# alexakit.net
KiCad netlist of a schematic drawn in EAGLE
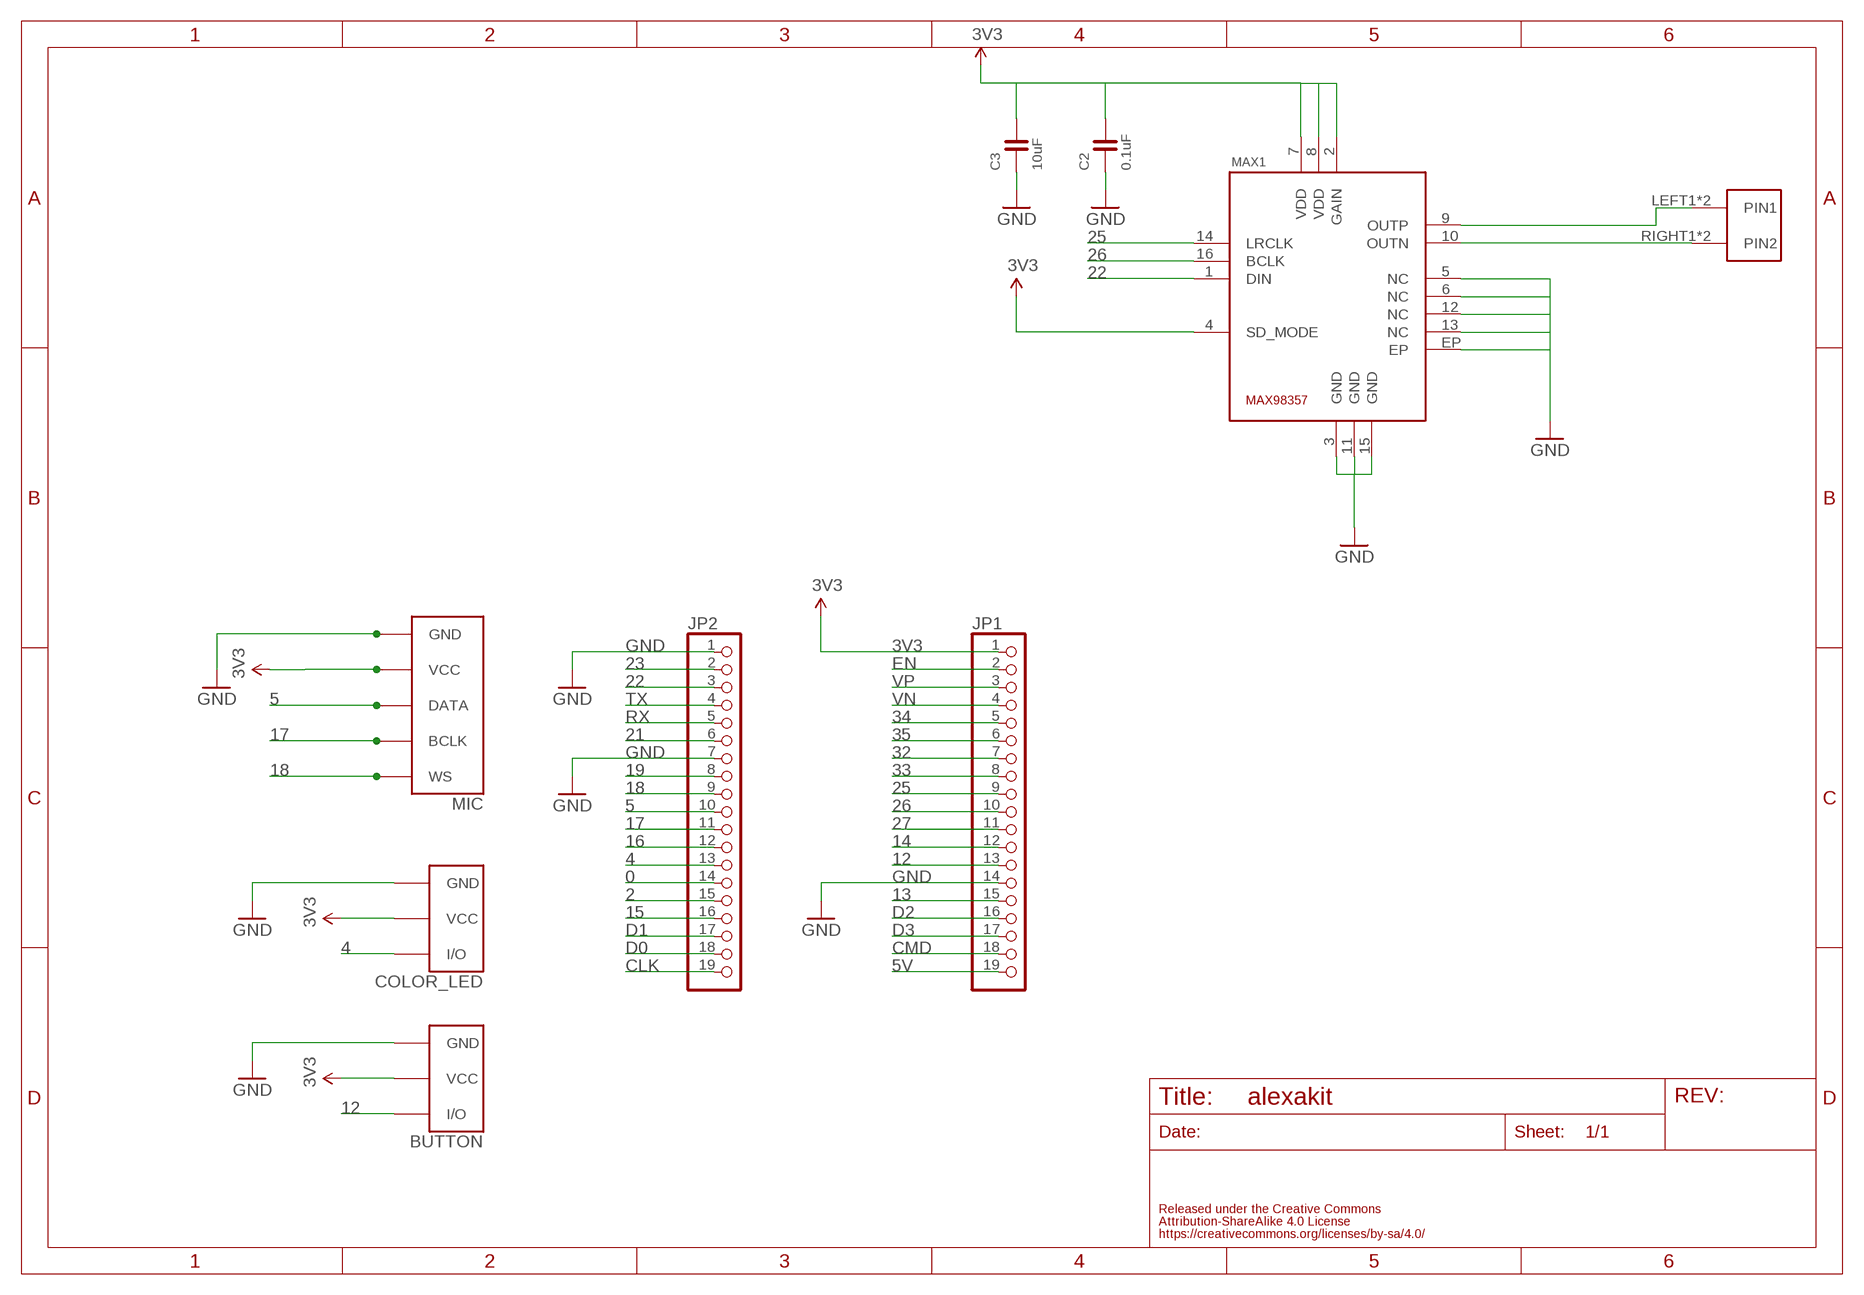
[diagram p0: schematic, sheet 1]

(export (version "E")
  (design (tool "Eeschema 10.0.6"))
  (components
    (comp (ref "BUTTON")
      (value "BUTTON")
      (footprint "eagle-import:FABO_BRICK_3PIN_B03B-PASK-1_NAME_BOTTOM")
      (libsource (lib "eagle-import") (part "FABO_BRICK_3PIN-03B-PASK-1_NAME_BOTTOM"))
    )
    (comp (ref "C2")
      (value "0.1uF")
      (footprint "eagle-import:0603")
      (libsource (lib "eagle-import") (part "CAPACITOR-0603"))
    )
    (comp (ref "C3")
      (value "10uF")
      (footprint "eagle-import:0603")
      (libsource (lib "eagle-import") (part "CAPACITOR-0603"))
    )
    (comp (ref "COLOR_LED")
      (value "FABO_BRICK_3PIN-03B-PASK-1_NAME_BOTTOM")
      (footprint "eagle-import:FABO_BRICK_3PIN_B03B-PASK-1_NAME_BOTTOM")
      (libsource (lib "eagle-import") (part "FABO_BRICK_3PIN-03B-PASK-1_NAME_BOTTOM"))
    )
    (comp (ref "JP1")
      (value "PINHD-1X19")
      (footprint "eagle-import:1X19")
      (libsource (lib "eagle-import") (part "PINHD-1X19"))
    )
    (comp (ref "JP2")
      (value "PINHD-1X19")
      (footprint "eagle-import:1X19")
      (libsource (lib "eagle-import") (part "PINHD-1X19"))
    )
    (comp (ref "MAX1")
      (value "MA-MAX98357")
      (footprint "eagle-import:MAXIM-MAX98357")
      (libsource (lib "eagle-import") (part "MA-MAX98357"))
    )
    (comp (ref "MIC")
      (value "FABO_BRICK_I2STOP")
      (footprint "eagle-import:FABO_BRICK_I2S_B05B-PARK-1")
      (libsource (lib "eagle-import") (part "FABO_BRICK_I2STOP"))
    )
    (comp (ref "U$4")
      (value "ML-1400-S1")
      (footprint "eagle-import:ML-1400-S1")
      (libsource (lib "eagle-import") (part "ML-1400-S1"))
    )
  )
  (nets
    (net (code "1") (name "/0") (class "Default")
      (node (ref "JP2") (pin "14") (pinfunction "14_14") (pintype "passive"))
    )
    (net (code "2") (name "/2") (class "Default")
      (node (ref "JP2") (pin "15") (pinfunction "15_15") (pintype "passive"))
    )
    (net (code "3") (name "/4") (class "Default")
      (node (ref "COLOR_LED") (pin "I/O") (pinfunction "I/O_I/O") (pintype "bidirectional"))
      (node (ref "JP2") (pin "13") (pinfunction "13_13") (pintype "passive"))
    )
    (net (code "4") (name "/5") (class "Default")
      (node (ref "JP2") (pin "10") (pinfunction "10_10") (pintype "passive"))
      (node (ref "MIC") (pin "DATA") (pinfunction "DATA_DATA") (pintype "bidirectional"))
    )
    (net (code "5") (name "/5V") (class "Default")
      (node (ref "JP1") (pin "19") (pinfunction "19_19") (pintype "passive"))
    )
    (net (code "6") (name "/12") (class "Default")
      (node (ref "BUTTON") (pin "I/O") (pinfunction "I/O_I/O") (pintype "bidirectional"))
      (node (ref "JP1") (pin "13") (pinfunction "13_13") (pintype "passive"))
    )
    (net (code "7") (name "/13") (class "Default")
      (node (ref "JP1") (pin "15") (pinfunction "15_15") (pintype "passive"))
    )
    (net (code "8") (name "/14") (class "Default")
      (node (ref "JP1") (pin "12") (pinfunction "12_12") (pintype "passive"))
    )
    (net (code "9") (name "/15") (class "Default")
      (node (ref "JP2") (pin "16") (pinfunction "16_16") (pintype "passive"))
    )
    (net (code "10") (name "/16") (class "Default")
      (node (ref "JP2") (pin "12") (pinfunction "12_12") (pintype "passive"))
    )
    (net (code "11") (name "/17") (class "Default")
      (node (ref "JP2") (pin "11") (pinfunction "11_11") (pintype "passive"))
      (node (ref "MIC") (pin "BCLK") (pinfunction "BCLK_BCLK") (pintype "bidirectional"))
    )
    (net (code "12") (name "/18") (class "Default")
      (node (ref "JP2") (pin "9") (pinfunction "9_9") (pintype "passive"))
      (node (ref "MIC") (pin "WS") (pinfunction "WS_WS") (pintype "bidirectional"))
    )
    (net (code "13") (name "/19") (class "Default")
      (node (ref "JP2") (pin "8") (pinfunction "8_8") (pintype "passive"))
    )
    (net (code "14") (name "/21") (class "Default")
      (node (ref "JP2") (pin "6") (pinfunction "6_6") (pintype "passive"))
    )
    (net (code "15") (name "/22") (class "Default")
      (node (ref "JP2") (pin "3") (pinfunction "3_3") (pintype "passive"))
      (node (ref "MAX1") (pin "1") (pinfunction "DIN_1") (pintype "bidirectional"))
    )
    (net (code "16") (name "/23") (class "Default")
      (node (ref "JP2") (pin "2") (pinfunction "2_2") (pintype "passive"))
    )
    (net (code "17") (name "/25") (class "Default")
      (node (ref "JP1") (pin "9") (pinfunction "9_9") (pintype "passive"))
      (node (ref "MAX1") (pin "14") (pinfunction "LRCLK_14") (pintype "bidirectional"))
    )
    (net (code "18") (name "/26") (class "Default")
      (node (ref "JP1") (pin "10") (pinfunction "10_10") (pintype "passive"))
      (node (ref "MAX1") (pin "16") (pinfunction "BCLK_16") (pintype "bidirectional"))
    )
    (net (code "19") (name "/27") (class "Default")
      (node (ref "JP1") (pin "11") (pinfunction "11_11") (pintype "passive"))
    )
    (net (code "20") (name "/32") (class "Default")
      (node (ref "JP1") (pin "7") (pinfunction "7_7") (pintype "passive"))
    )
    (net (code "21") (name "/33") (class "Default")
      (node (ref "JP1") (pin "8") (pinfunction "8_8") (pintype "passive"))
    )
    (net (code "22") (name "/34") (class "Default")
      (node (ref "JP1") (pin "5") (pinfunction "5_5") (pintype "passive"))
    )
    (net (code "23") (name "/35") (class "Default")
      (node (ref "JP1") (pin "6") (pinfunction "6_6") (pintype "passive"))
    )
    (net (code "24") (name "/CLK") (class "Default")
      (node (ref "JP2") (pin "19") (pinfunction "19_19") (pintype "passive"))
    )
    (net (code "25") (name "/CMD") (class "Default")
      (node (ref "JP1") (pin "18") (pinfunction "18_18") (pintype "passive"))
    )
    (net (code "26") (name "/D0") (class "Default")
      (node (ref "JP2") (pin "18") (pinfunction "18_18") (pintype "passive"))
    )
    (net (code "27") (name "/D1") (class "Default")
      (node (ref "JP2") (pin "17") (pinfunction "17_17") (pintype "passive"))
    )
    (net (code "28") (name "/D2") (class "Default")
      (node (ref "JP1") (pin "16") (pinfunction "16_16") (pintype "passive"))
    )
    (net (code "29") (name "/D3") (class "Default")
      (node (ref "JP1") (pin "17") (pinfunction "17_17") (pintype "passive"))
    )
    (net (code "30") (name "/EN") (class "Default")
      (node (ref "JP1") (pin "2") (pinfunction "2_2") (pintype "passive"))
    )
    (net (code "31") (name "/RX") (class "Default")
      (node (ref "JP2") (pin "5") (pinfunction "5_5") (pintype "passive"))
    )
    (net (code "32") (name "/TX") (class "Default")
      (node (ref "JP2") (pin "4") (pinfunction "4_4") (pintype "passive"))
    )
    (net (code "33") (name "/VN") (class "Default")
      (node (ref "JP1") (pin "4") (pinfunction "4_4") (pintype "passive"))
    )
    (net (code "34") (name "/VP") (class "Default")
      (node (ref "JP1") (pin "3") (pinfunction "3_3") (pintype "passive"))
    )
    (net (code "35") (name "3V3") (class "Default")
      (node (ref "BUTTON") (pin "VCC") (pinfunction "VCC_VCC") (pintype "bidirectional"))
      (node (ref "C2") (pin "2") (pinfunction "2_2") (pintype "passive"))
      (node (ref "C3") (pin "2") (pinfunction "2_2") (pintype "passive"))
      (node (ref "COLOR_LED") (pin "VCC") (pinfunction "VCC_VCC") (pintype "bidirectional"))
      (node (ref "JP1") (pin "1") (pinfunction "1_1") (pintype "passive"))
      (node (ref "MAX1") (pin "2") (pinfunction "GAIN_2") (pintype "bidirectional"))
      (node (ref "MAX1") (pin "4") (pinfunction "SD_MODE_4") (pintype "bidirectional"))
      (node (ref "MAX1") (pin "7") (pinfunction "VDD_7") (pintype "bidirectional"))
      (node (ref "MAX1") (pin "8") (pinfunction "VDD_8") (pintype "bidirectional"))
      (node (ref "MIC") (pin "VCC") (pinfunction "VCC_VCC") (pintype "bidirectional"))
    )
    (net (code "36") (name "GND") (class "Default")
      (node (ref "BUTTON") (pin "GND") (pinfunction "GND_GND") (pintype "bidirectional"))
      (node (ref "C2") (pin "1") (pinfunction "1_1") (pintype "passive"))
      (node (ref "C3") (pin "1") (pinfunction "1_1") (pintype "passive"))
      (node (ref "COLOR_LED") (pin "GND") (pinfunction "GND_GND") (pintype "bidirectional"))
      (node (ref "JP1") (pin "14") (pinfunction "14_14") (pintype "passive"))
      (node (ref "JP2") (pin "1") (pinfunction "1_1") (pintype "passive"))
      (node (ref "JP2") (pin "7") (pinfunction "7_7") (pintype "passive"))
      (node (ref "MAX1") (pin "11") (pinfunction "GND_11") (pintype "bidirectional"))
      (node (ref "MAX1") (pin "12") (pinfunction "NC_12") (pintype "bidirectional"))
      (node (ref "MAX1") (pin "13") (pinfunction "NC_13") (pintype "bidirectional"))
      (node (ref "MAX1") (pin "15") (pinfunction "GND_15") (pintype "bidirectional"))
      (node (ref "MAX1") (pin "3") (pinfunction "GND_3") (pintype "bidirectional"))
      (node (ref "MAX1") (pin "5") (pinfunction "NC_5") (pintype "bidirectional"))
      (node (ref "MAX1") (pin "6") (pinfunction "NC_6") (pintype "bidirectional"))
      (node (ref "MAX1") (pin "EP") (pinfunction "EP_EP") (pintype "bidirectional"))
      (node (ref "MIC") (pin "GND") (pinfunction "GND_GND") (pintype "bidirectional"))
    )
    (net (code "37") (name "Net-(MAX1-OUTN)") (class "Default")
      (node (ref "MAX1") (pin "10") (pinfunction "OUTN_10") (pintype "bidirectional"))
      (node (ref "U$4") (pin "RIGHT1") (pinfunction "PIN2_RIGHT1") (pintype "bidirectional"))
      (node (ref "U$4") (pin "RIGHT2") (pinfunction "PIN2_RIGHT2") (pintype "bidirectional"))
    )
    (net (code "38") (name "Net-(MAX1-OUTP)") (class "Default")
      (node (ref "MAX1") (pin "9") (pinfunction "OUTP_9") (pintype "bidirectional"))
      (node (ref "U$4") (pin "LEFT1") (pinfunction "PIN1_LEFT1") (pintype "bidirectional"))
      (node (ref "U$4") (pin "LEFT2") (pinfunction "PIN1_LEFT2") (pintype "bidirectional"))
    )
  )
)
